# Simple-Charger-LiIon-OpampBased-LM324-Re.net
KiCad netlist of a schematic drawn in EAGLE
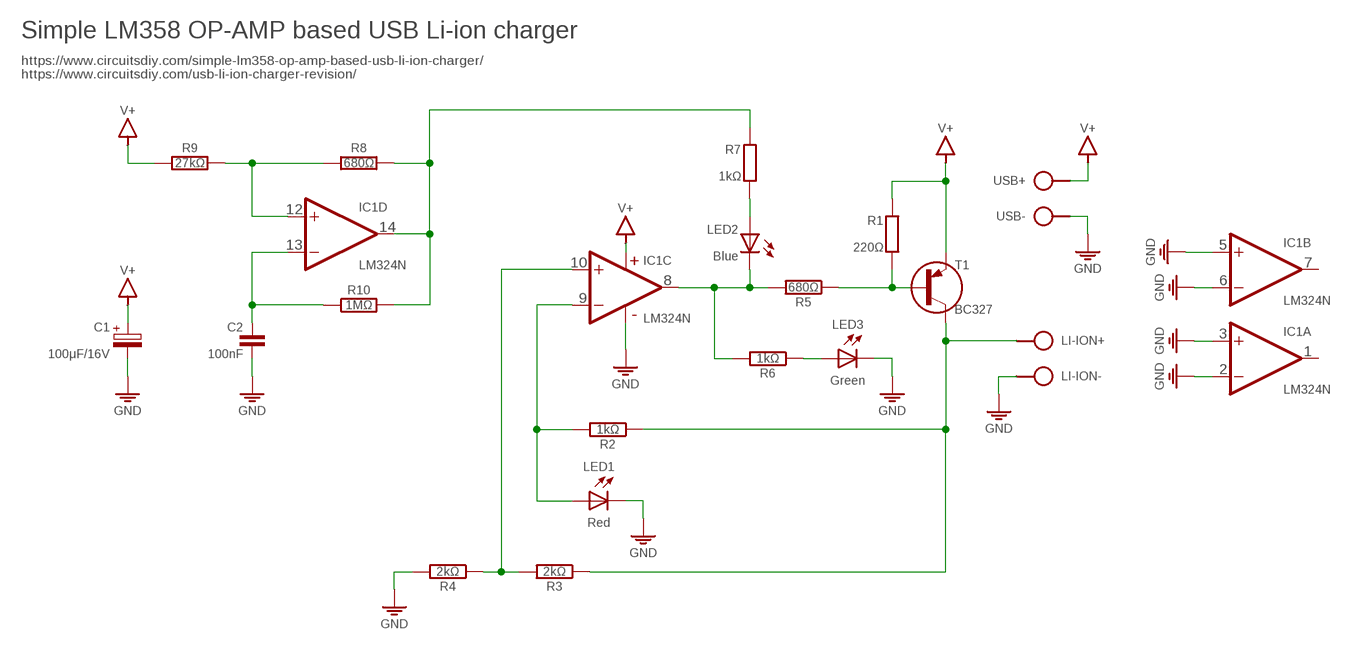
[diagram p0: schematic, sheet 1]

(export (version "E")
  (design (tool "Eeschema 10.0.6"))
  (components
    (comp (ref "C1")
      (value "100μF/16V")
      (footprint "eagle-import:E2,5-5")
      (libsource (lib "eagle-import") (part "CPOLE2.5-5"))
    )
    (comp (ref "C2")
      (value "100nF")
      (footprint "eagle-import:C050-020X044_V")
      (libsource (lib "eagle-import") (part "C050-020X044/V"))
    )
    (comp (ref "IC1")
      (value "LM324N")
      (footprint "eagle-import:DIL14")
      (libsource (lib "eagle-import") (part "LM324N"))
    )
    (comp (ref "LED1")
      (value "Red")
      (footprint "eagle-import:LED_3MM")
      (libsource (lib "eagle-import") (part "LED-H-3MM"))
    )
    (comp (ref "LED2")
      (value "Blue")
      (footprint "eagle-import:LED_3MM")
      (libsource (lib "eagle-import") (part "LED-3MM"))
    )
    (comp (ref "LED3")
      (value "Green")
      (footprint "eagle-import:LED_3MM")
      (libsource (lib "eagle-import") (part "LED-H-3MM"))
    )
    (comp (ref "LI-ION")
      (value "SPAD+-+-")
      (footprint "eagle-import:SPAD+-")
      (libsource (lib "eagle-import") (part "SPAD+-+-"))
    )
    (comp (ref "R1")
      (value "220Ω")
      (footprint "eagle-import:0204_10-V")
      (libsource (lib "eagle-import") (part "R0204/10-V"))
    )
    (comp (ref "R2")
      (value "1kΩ")
      (footprint "eagle-import:0204_10")
      (libsource (lib "eagle-import") (part "R-H0204/10"))
    )
    (comp (ref "R3")
      (value "2kΩ")
      (footprint "eagle-import:0204_10")
      (libsource (lib "eagle-import") (part "R-H0204/10"))
    )
    (comp (ref "R4")
      (value "2kΩ")
      (footprint "eagle-import:0204_12-V")
      (libsource (lib "eagle-import") (part "R-H0204/12-V"))
    )
    (comp (ref "R5")
      (value "680Ω")
      (footprint "eagle-import:0204_10")
      (libsource (lib "eagle-import") (part "R-H0204/10"))
    )
    (comp (ref "R6")
      (value "1kΩ")
      (footprint "eagle-import:0204_10")
      (libsource (lib "eagle-import") (part "R-H0204/10"))
    )
    (comp (ref "R7")
      (value "1kΩ")
      (footprint "eagle-import:0204_10")
      (libsource (lib "eagle-import") (part "R0204/10"))
    )
    (comp (ref "R8")
      (value "680Ω")
      (footprint "eagle-import:0204_10")
      (libsource (lib "eagle-import") (part "R-H0204/10"))
    )
    (comp (ref "R9")
      (value "27kΩ")
      (footprint "eagle-import:0204_10")
      (libsource (lib "eagle-import") (part "R-H0204/10"))
    )
    (comp (ref "R10")
      (value "1MΩ")
      (footprint "eagle-import:0204_2.54")
      (libsource (lib "eagle-import") (part "R-H0204/2.54"))
    )
    (comp (ref "T1")
      (value "BC327")
      (footprint "eagle-import:TO92")
      (libsource (lib "eagle-import") (part "BC327"))
    )
    (comp (ref "USB")
      (value "SPAD+--+")
      (footprint "eagle-import:SPAD-+")
      (libsource (lib "eagle-import") (part "SPAD+--+"))
    )
  )
  (nets
    (net (code "1") (name "GND") (class "Default")
      (node (ref "C1") (pin "-") (pinfunction "-_-") (pintype "passive"))
      (node (ref "C2") (pin "2") (pinfunction "2_2") (pintype "passive"))
      (node (ref "IC1") (pin "11") (pinfunction "V-_11") (pintype "power_in"))
      (node (ref "IC1") (pin "2") (pinfunction "-IN_2") (pintype "input"))
      (node (ref "IC1") (pin "3") (pinfunction "+IN_3") (pintype "input"))
      (node (ref "IC1") (pin "5") (pinfunction "+IN_5") (pintype "input"))
      (node (ref "IC1") (pin "6") (pinfunction "-IN_6") (pintype "input"))
      (node (ref "LED1") (pin "K") (pinfunction "K_K") (pintype "passive"))
      (node (ref "LED3") (pin "K") (pinfunction "K_K") (pintype "passive"))
      (node (ref "LI-ION") (pin "1") (pinfunction "P$1_1") (pintype "passive"))
      (node (ref "R4") (pin "2") (pinfunction "2_2") (pintype "passive"))
      (node (ref "USB") (pin "1") (pinfunction "P$1_1") (pintype "passive"))
    )
    (net (code "2") (name "Net-(IC1C-+IN)") (class "Default")
      (node (ref "IC1") (pin "10") (pinfunction "+IN_10") (pintype "input"))
      (node (ref "R3") (pin "2") (pinfunction "2_2") (pintype "passive"))
      (node (ref "R4") (pin "1") (pinfunction "1_1") (pintype "passive"))
    )
    (net (code "3") (name "Net-(IC1C--IN)") (class "Default")
      (node (ref "IC1") (pin "9") (pinfunction "-IN_9") (pintype "input"))
      (node (ref "LED1") (pin "A") (pinfunction "A_A") (pintype "passive"))
      (node (ref "R2") (pin "2") (pinfunction "2_2") (pintype "passive"))
    )
    (net (code "4") (name "Net-(IC1C-OUT)") (class "Default")
      (node (ref "IC1") (pin "8") (pinfunction "OUT_8") (pintype "output"))
      (node (ref "LED2") (pin "K") (pinfunction "K_K") (pintype "passive"))
      (node (ref "R5") (pin "2") (pinfunction "2_2") (pintype "passive"))
      (node (ref "R6") (pin "2") (pinfunction "2_2") (pintype "passive"))
    )
    (net (code "5") (name "Net-(IC1D-+IN)") (class "Default")
      (node (ref "IC1") (pin "12") (pinfunction "+IN_12") (pintype "input"))
      (node (ref "R8") (pin "2") (pinfunction "2_2") (pintype "passive"))
      (node (ref "R9") (pin "2") (pinfunction "2_2") (pintype "passive"))
    )
    (net (code "6") (name "Net-(IC1D--IN)") (class "Default")
      (node (ref "C2") (pin "1") (pinfunction "1_1") (pintype "passive"))
      (node (ref "IC1") (pin "13") (pinfunction "-IN_13") (pintype "input"))
      (node (ref "R10") (pin "1") (pinfunction "1_1") (pintype "passive"))
    )
    (net (code "7") (name "Net-(IC1D-OUT)") (class "Default")
      (node (ref "IC1") (pin "14") (pinfunction "OUT_14") (pintype "output"))
      (node (ref "R10") (pin "2") (pinfunction "2_2") (pintype "passive"))
      (node (ref "R7") (pin "1") (pinfunction "1_1") (pintype "passive"))
      (node (ref "R8") (pin "1") (pinfunction "1_1") (pintype "passive"))
    )
    (net (code "8") (name "Net-(LED2-PadA)") (class "Default")
      (node (ref "LED2") (pin "A") (pinfunction "A_A") (pintype "passive"))
      (node (ref "R7") (pin "2") (pinfunction "2_2") (pintype "passive"))
    )
    (net (code "9") (name "Net-(LED3-PadA)") (class "Default")
      (node (ref "LED3") (pin "A") (pinfunction "A_A") (pintype "passive"))
      (node (ref "R6") (pin "1") (pinfunction "1_1") (pintype "passive"))
    )
    (net (code "10") (name "Net-(LI-IONA-P$1)") (class "Default")
      (node (ref "LI-ION") (pin "2") (pinfunction "P$1_2") (pintype "passive"))
      (node (ref "R2") (pin "1") (pinfunction "1_1") (pintype "passive"))
      (node (ref "R3") (pin "1") (pinfunction "1_1") (pintype "passive"))
      (node (ref "T1") (pin "1") (pinfunction "C_1") (pintype "passive"))
    )
    (net (code "11") (name "Net-(T1-B)") (class "Default")
      (node (ref "R1") (pin "2") (pinfunction "2_2") (pintype "passive"))
      (node (ref "R5") (pin "1") (pinfunction "1_1") (pintype "passive"))
      (node (ref "T1") (pin "2") (pinfunction "B_2") (pintype "passive"))
    )
    (net (code "12") (name "V+") (class "Default")
      (node (ref "C1") (pin "+") (pinfunction "+_+") (pintype "passive"))
      (node (ref "IC1") (pin "4") (pinfunction "V+_4") (pintype "power_in"))
      (node (ref "R1") (pin "1") (pinfunction "1_1") (pintype "passive"))
      (node (ref "R9") (pin "1") (pinfunction "1_1") (pintype "passive"))
      (node (ref "T1") (pin "3") (pinfunction "E_3") (pintype "passive"))
      (node (ref "USB") (pin "2") (pinfunction "P$1_2") (pintype "passive"))
    )
    (net (code "13") (name "unconnected-(IC1A-OUT-Pad1)") (class "Default")
      (node (ref "IC1") (pin "1") (pinfunction "OUT_1") (pintype "output"))
    )
    (net (code "14") (name "unconnected-(IC1B-OUT-Pad7)") (class "Default")
      (node (ref "IC1") (pin "7") (pinfunction "OUT_7") (pintype "output"))
    )
  )
)
